# 04_MCU.net
KiCad netlist of a schematic drawn in Altium Designer
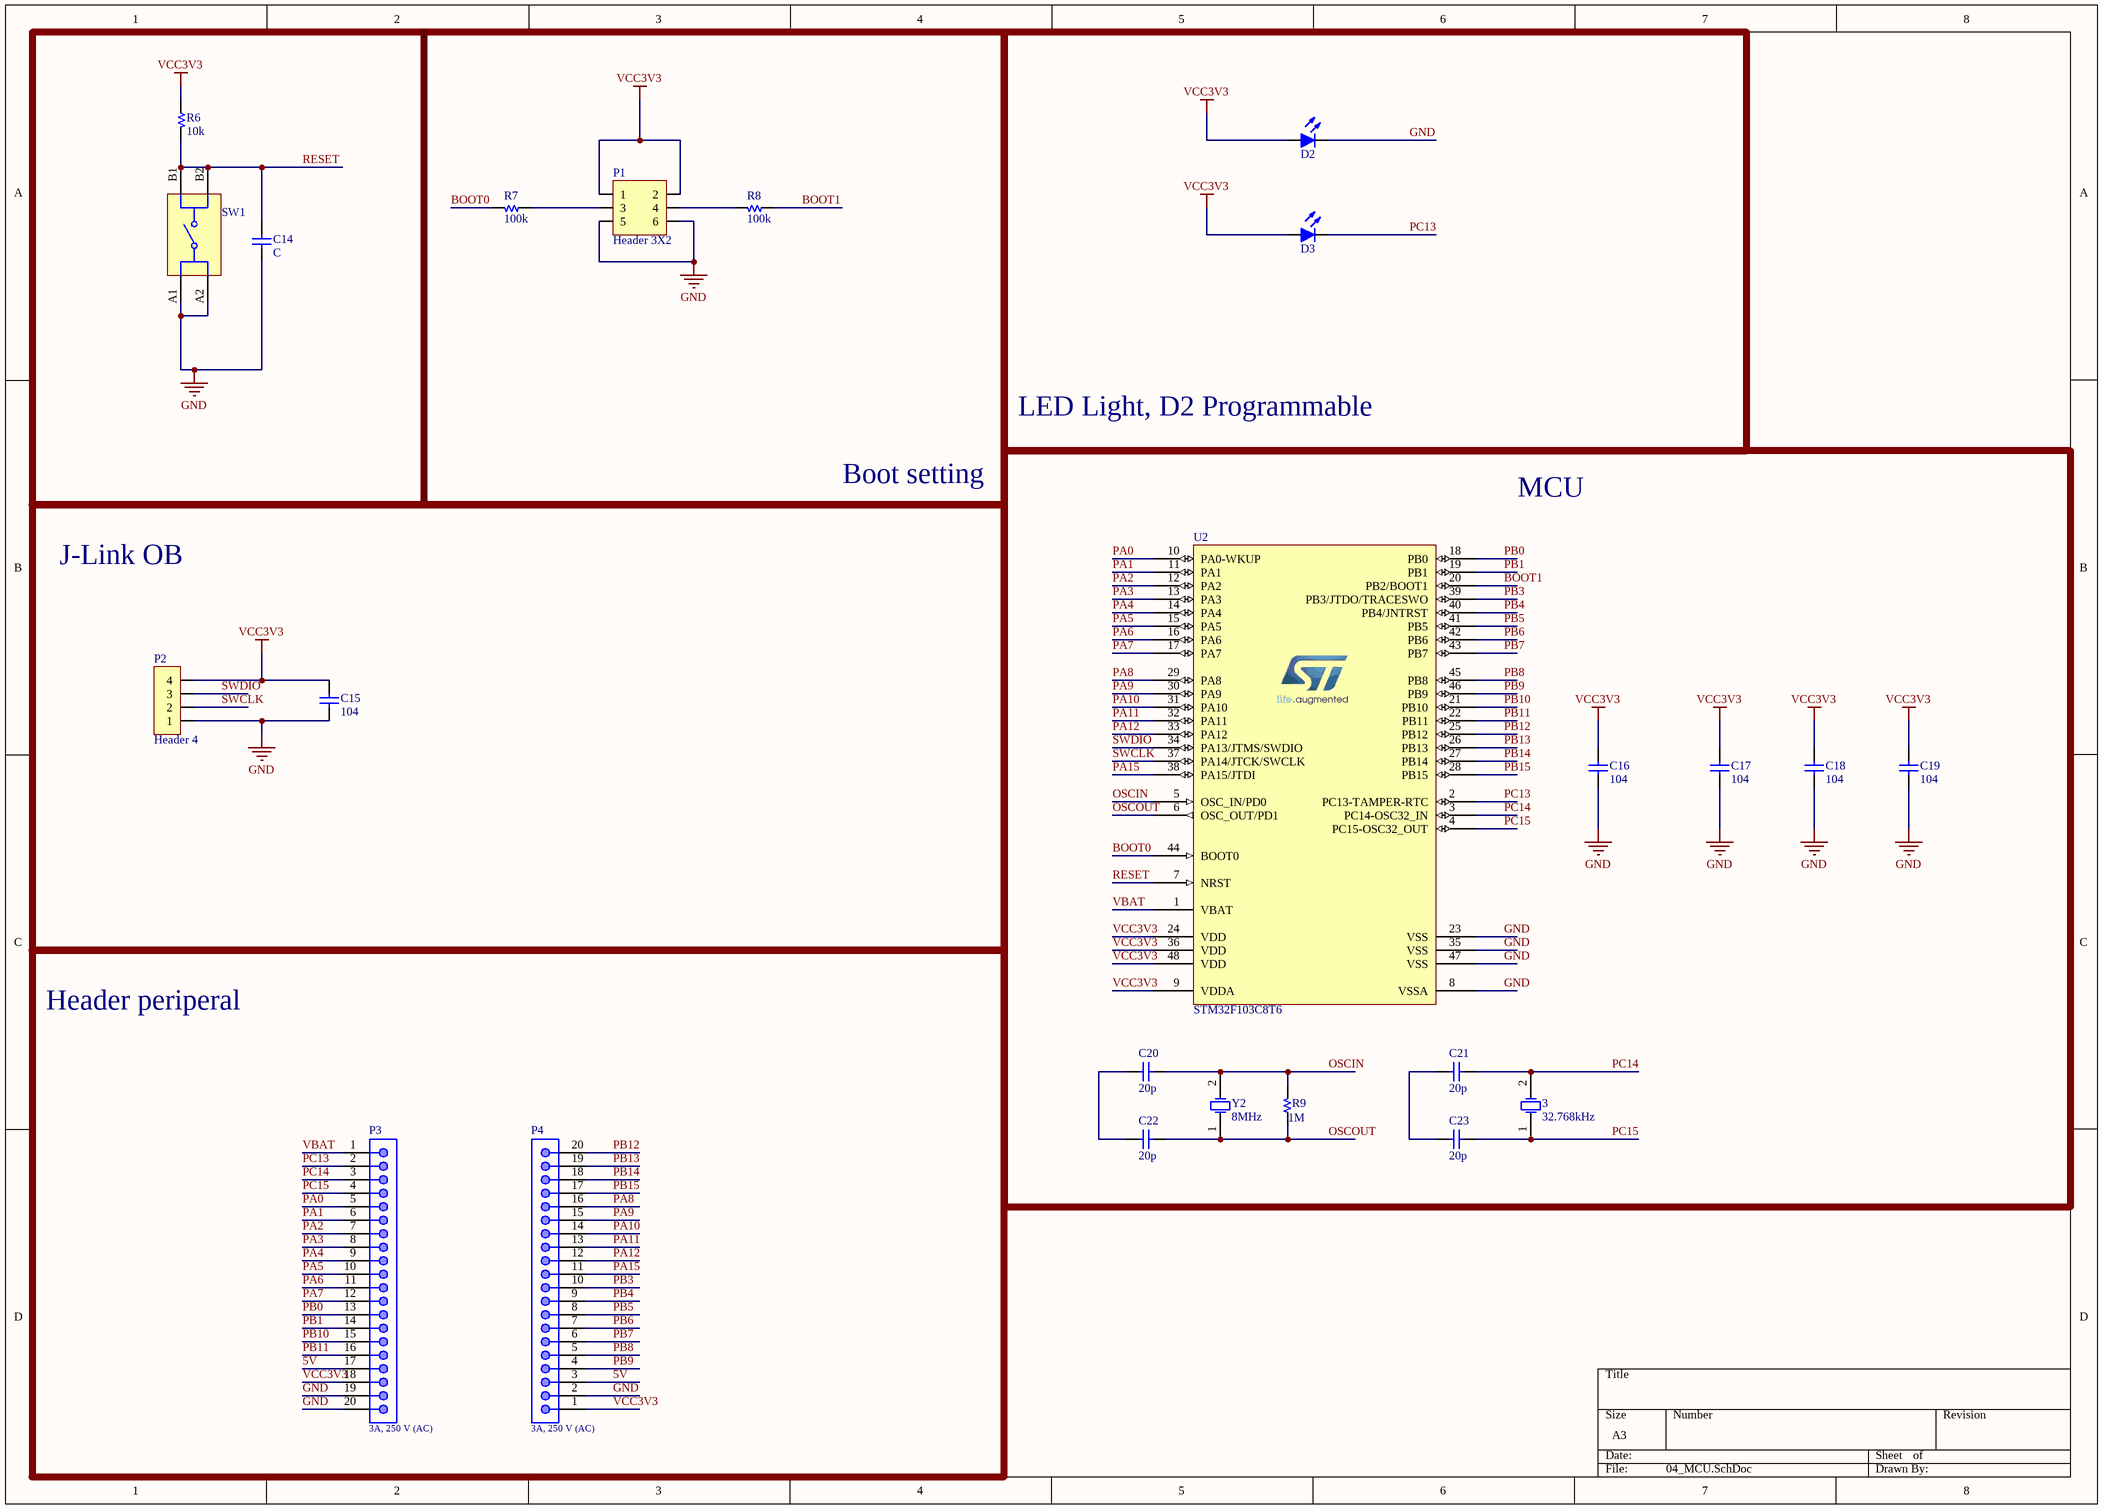
[diagram p0: 04_MCU.SchDoc]

(export (version "E")
  (design (tool "Eeschema 10.0.6"))
  (components
    (comp (ref "3")
      (value "32.768kHz")
      (footprint "XKXGI-SUA-32.768K")
      (description "32.768kHz Surface Mount Crystal 12.5pF ±20ppm ±30ppm SMD3215-2P Crystals ROHS")
      (fields (field (name "LCSC PART #") "C5213671") (field (name "MANUFACTURER") "YXC Crystal Oscillators"))
      (libsource (lib "Altium_XTAL_WATCH") (part "XKXGI-SUA-32.768K"))
    )
    (comp (ref "C14")
      (value "C")
      (footprint "C 0805")
      (description "Capacitor non-pol")
      (libsource (lib "chipfc_libs") (part "Capacitor NP"))
    )
    (comp (ref "C15")
      (value "104")
      (footprint "C 0805")
      (description "Capacitor non-pol")
      (libsource (lib "chipfc_libs") (part "Capacitor NP"))
    )
    (comp (ref "C16")
      (value "104")
      (footprint "C 0805")
      (description "Capacitor non-pol")
      (libsource (lib "chipfc_libs") (part "Capacitor NP"))
    )
    (comp (ref "C17")
      (value "104")
      (footprint "C 0805")
      (description "Capacitor non-pol")
      (libsource (lib "chipfc_libs") (part "Capacitor NP"))
    )
    (comp (ref "C18")
      (value "104")
      (footprint "C 0805")
      (description "Capacitor non-pol")
      (libsource (lib "chipfc_libs") (part "Capacitor NP"))
    )
    (comp (ref "C19")
      (value "104")
      (footprint "C 0805")
      (description "Capacitor non-pol")
      (libsource (lib "chipfc_libs") (part "Capacitor NP"))
    )
    (comp (ref "C20")
      (value "20p")
      (footprint "C 0805")
      (description "Capacitor non-pol")
      (libsource (lib "chipfc_libs") (part "Capacitor NP"))
    )
    (comp (ref "C21")
      (value "20p")
      (footprint "C 0805")
      (description "Capacitor non-pol")
      (libsource (lib "chipfc_libs") (part "Capacitor NP"))
    )
    (comp (ref "C22")
      (value "20p")
      (footprint "C 0805")
      (description "Capacitor non-pol")
      (libsource (lib "chipfc_libs") (part "Capacitor NP"))
    )
    (comp (ref "C23")
      (value "20p")
      (footprint "C 0805")
      (description "Capacitor non-pol")
      (libsource (lib "chipfc_libs") (part "Capacitor NP"))
    )
    (comp (ref "D2")
      (value "Led")
      (footprint "Led 0805")
      (description "Typical LED")
      (libsource (lib "led") (part "Led"))
    )
    (comp (ref "D3")
      (value "Led")
      (footprint "Led 0805")
      (description "Typical LED")
      (libsource (lib "led") (part "Led"))
    )
    (comp (ref "P1")
      (value "Header 3X2")
      (footprint "HDR/Header/6/DL")
      (description "Header, 3-Pin, Dual row")
      (libsource (lib "connectors") (part "Header 3X2"))
    )
    (comp (ref "P2")
      (value "Header 4")
      (footprint "HDR/Header/4")
      (description "Header, 4-Pin")
      (libsource (lib "connectors") (part "Header 4"))
    )
    (comp (ref "P3")
      (value "3A, 250 V (AC)")
      (footprint "61302011121")
      (description "WR-PHD Pin Header, THT, pitch 2.54mm, Single Row, Vertical, 20p")
      (fields
        (field (name "MANUFACTURER PART NUMBER") "61302011121")
        (field (name "MANUFACTURER") "Wurth Elektronik")
      )
      (libsource (lib "WR-PHD_Pin Header_2.54mm") (part "61302011121"))
    )
    (comp (ref "P4")
      (value "3A, 250 V (AC)")
      (footprint "61302011121")
      (description "WR-PHD Pin Header, THT, pitch 2.54mm, Single Row, Vertical, 20p")
      (fields
        (field (name "MANUFACTURER PART NUMBER") "61302011121")
        (field (name "MANUFACTURER") "Wurth Elektronik")
      )
      (libsource (lib "WR-PHD_Pin Header_2.54mm") (part "61302011121"))
    )
    (comp (ref "R6")
      (value "10k")
      (footprint "R 0805")
      (description "Resistor")
      (libsource (lib "chipfc_libs") (part "Resistor"))
    )
    (comp (ref "R7")
      (value "100k")
      (footprint "R 0805")
      (description "Resistor")
      (libsource (lib "chipfc_libs") (part "Resistor"))
    )
    (comp (ref "R8")
      (value "100k")
      (footprint "R 0805")
      (description "Resistor")
      (libsource (lib "chipfc_libs") (part "Resistor"))
    )
    (comp (ref "R9")
      (value "1M")
      (footprint "R 0805")
      (description "Resistor")
      (libsource (lib "chipfc_libs") (part "Resistor"))
    )
    (comp (ref "SW1")
      (value "430152043826")
      (footprint "WS-TASV_L6W6H4.3_4301x20438x6")
      (description "WS-TASV SMT Tact Switch, L6 x W6 x H4.3mm, 260g, SPST-NO, 12V, 50mA")
      (fields (field (name "MANUFACTURER") "Wurth Elektronik"))
      (libsource (lib "Button") (part "430152043826"))
    )
    (comp (ref "U2")
      (value "STM32F103C8T6")
      (footprint "STM32F103C8T6")
      (description "ARM Microcontrollers - MCU 32BIT Cortex M3 64KB 20KB RAM 2X12 ADC")
      (fields
        (field (name "MANUFACTURER") "STMicroelectronics")
        (field (name "MANUFACTURER PART NUMBER") "STM32F103C8T6TR")
      )
      (libsource (lib "STM32") (part "STM32F103C8T6"))
    )
    (comp (ref "Y2")
      (value "8MHz")
      (footprint "WE-XTAL_HC49/4HSMX")
      (description "WE-XTAL Quartz Crystal, SMT, HC49/4HSMX, 8MHz, +/-30ppm")
      (fields
        (field (name "MANUFACTURER PART NUMBER") "830003151")
        (field (name "MANUFACTURER") "Wurth Elektronik")
      )
      (libsource (lib "Altium_XTAL_2PIN") (part "071105086016"))
    )
  )
  (nets
    (net (code "1") (name "/5V") (class "Default")
      (node (ref "P3") (pin "17") (pinfunction "17_17") (pintype "passive"))
      (node (ref "P4") (pin "3") (pinfunction "3_3") (pintype "passive"))
    )
    (net (code "2") (name "/BOOT0") (class "Default")
      (node (ref "R7") (pin "2") (pinfunction "2_2") (pintype "passive"))
      (node (ref "U2") (pin "44") (pinfunction "BOOT0_44") (pintype "input"))
    )
    (net (code "3") (name "/BOOT1") (class "Default")
      (node (ref "R8") (pin "1") (pinfunction "1_1") (pintype "passive"))
      (node (ref "U2") (pin "20") (pinfunction "PB2/BOOT1_20") (pintype "bidirectional"))
    )
    (net (code "4") (name "/OSCIN") (class "Default")
      (node (ref "C20") (pin "1") (pinfunction "1_1") (pintype "passive"))
      (node (ref "R9") (pin "2") (pinfunction "2_2") (pintype "passive"))
      (node (ref "U2") (pin "5") (pinfunction "OSC_IN/PD0_5") (pintype "input"))
      (node (ref "Y2") (pin "2") (pinfunction "OSC2_2") (pintype "passive"))
    )
    (net (code "5") (name "/OSCOUT") (class "Default")
      (node (ref "C22") (pin "1") (pinfunction "1_1") (pintype "passive"))
      (node (ref "R9") (pin "1") (pinfunction "1_1") (pintype "passive"))
      (node (ref "U2") (pin "6") (pinfunction "OSC_OUT/PD1_6") (pintype "output"))
      (node (ref "Y2") (pin "1") (pinfunction "OSC1_1") (pintype "passive"))
    )
    (net (code "6") (name "/PA0") (class "Default")
      (node (ref "P3") (pin "5") (pinfunction "5_5") (pintype "passive"))
      (node (ref "U2") (pin "10") (pinfunction "PA0-WKUP_10") (pintype "bidirectional"))
    )
    (net (code "7") (name "/PA1") (class "Default")
      (node (ref "P3") (pin "6") (pinfunction "6_6") (pintype "passive"))
      (node (ref "U2") (pin "11") (pinfunction "PA1_11") (pintype "bidirectional"))
    )
    (net (code "8") (name "/PA2") (class "Default")
      (node (ref "P3") (pin "7") (pinfunction "7_7") (pintype "passive"))
      (node (ref "U2") (pin "12") (pinfunction "PA2_12") (pintype "bidirectional"))
    )
    (net (code "9") (name "/PA3") (class "Default")
      (node (ref "P3") (pin "8") (pinfunction "8_8") (pintype "passive"))
      (node (ref "U2") (pin "13") (pinfunction "PA3_13") (pintype "bidirectional"))
    )
    (net (code "10") (name "/PA4") (class "Default")
      (node (ref "P3") (pin "9") (pinfunction "9_9") (pintype "passive"))
      (node (ref "U2") (pin "14") (pinfunction "PA4_14") (pintype "bidirectional"))
    )
    (net (code "11") (name "/PA5") (class "Default")
      (node (ref "P3") (pin "10") (pinfunction "10_10") (pintype "passive"))
      (node (ref "U2") (pin "15") (pinfunction "PA5_15") (pintype "bidirectional"))
    )
    (net (code "12") (name "/PA6") (class "Default")
      (node (ref "P3") (pin "11") (pinfunction "11_11") (pintype "passive"))
      (node (ref "U2") (pin "16") (pinfunction "PA6_16") (pintype "bidirectional"))
    )
    (net (code "13") (name "/PA7") (class "Default")
      (node (ref "P3") (pin "12") (pinfunction "12_12") (pintype "passive"))
      (node (ref "U2") (pin "17") (pinfunction "PA7_17") (pintype "bidirectional"))
    )
    (net (code "14") (name "/PA8") (class "Default")
      (node (ref "P4") (pin "16") (pinfunction "16_16") (pintype "passive"))
      (node (ref "U2") (pin "29") (pinfunction "PA8_29") (pintype "bidirectional"))
    )
    (net (code "15") (name "/PA9") (class "Default")
      (node (ref "P4") (pin "15") (pinfunction "15_15") (pintype "passive"))
      (node (ref "U2") (pin "30") (pinfunction "PA9_30") (pintype "bidirectional"))
    )
    (net (code "16") (name "/PA10") (class "Default")
      (node (ref "P4") (pin "14") (pinfunction "14_14") (pintype "passive"))
      (node (ref "U2") (pin "31") (pinfunction "PA10_31") (pintype "bidirectional"))
    )
    (net (code "17") (name "/PA11") (class "Default")
      (node (ref "P4") (pin "13") (pinfunction "13_13") (pintype "passive"))
      (node (ref "U2") (pin "32") (pinfunction "PA11_32") (pintype "bidirectional"))
    )
    (net (code "18") (name "/PA12") (class "Default")
      (node (ref "P4") (pin "12") (pinfunction "12_12") (pintype "passive"))
      (node (ref "U2") (pin "33") (pinfunction "PA12_33") (pintype "bidirectional"))
    )
    (net (code "19") (name "/PA15") (class "Default")
      (node (ref "P4") (pin "11") (pinfunction "11_11") (pintype "passive"))
      (node (ref "U2") (pin "38") (pinfunction "PA15/JTDI_38") (pintype "bidirectional"))
    )
    (net (code "20") (name "/PB0") (class "Default")
      (node (ref "P3") (pin "13") (pinfunction "13_13") (pintype "passive"))
      (node (ref "U2") (pin "18") (pinfunction "PB0_18") (pintype "bidirectional"))
    )
    (net (code "21") (name "/PB1") (class "Default")
      (node (ref "P3") (pin "14") (pinfunction "14_14") (pintype "passive"))
      (node (ref "U2") (pin "19") (pinfunction "PB1_19") (pintype "bidirectional"))
    )
    (net (code "22") (name "/PB3") (class "Default")
      (node (ref "P4") (pin "10") (pinfunction "10_10") (pintype "passive"))
      (node (ref "U2") (pin "39") (pinfunction "PB3/JTDO/TRACESWO_39") (pintype "bidirectional"))
    )
    (net (code "23") (name "/PB4") (class "Default")
      (node (ref "P4") (pin "9") (pinfunction "9_9") (pintype "passive"))
      (node (ref "U2") (pin "40") (pinfunction "PB4/JNTRST_40") (pintype "bidirectional"))
    )
    (net (code "24") (name "/PB5") (class "Default")
      (node (ref "P4") (pin "8") (pinfunction "8_8") (pintype "passive"))
      (node (ref "U2") (pin "41") (pinfunction "PB5_41") (pintype "bidirectional"))
    )
    (net (code "25") (name "/PB6") (class "Default")
      (node (ref "P4") (pin "7") (pinfunction "7_7") (pintype "passive"))
      (node (ref "U2") (pin "42") (pinfunction "PB6_42") (pintype "bidirectional"))
    )
    (net (code "26") (name "/PB7") (class "Default")
      (node (ref "P4") (pin "6") (pinfunction "6_6") (pintype "passive"))
      (node (ref "U2") (pin "43") (pinfunction "PB7_43") (pintype "bidirectional"))
    )
    (net (code "27") (name "/PB8") (class "Default")
      (node (ref "P4") (pin "5") (pinfunction "5_5") (pintype "passive"))
      (node (ref "U2") (pin "45") (pinfunction "PB8_45") (pintype "bidirectional"))
    )
    (net (code "28") (name "/PB9") (class "Default")
      (node (ref "P4") (pin "4") (pinfunction "4_4") (pintype "passive"))
      (node (ref "U2") (pin "46") (pinfunction "PB9_46") (pintype "bidirectional"))
    )
    (net (code "29") (name "/PB10") (class "Default")
      (node (ref "P3") (pin "15") (pinfunction "15_15") (pintype "passive"))
      (node (ref "U2") (pin "21") (pinfunction "PB10_21") (pintype "bidirectional"))
    )
    (net (code "30") (name "/PB11") (class "Default")
      (node (ref "P3") (pin "16") (pinfunction "16_16") (pintype "passive"))
      (node (ref "U2") (pin "22") (pinfunction "PB11_22") (pintype "bidirectional"))
    )
    (net (code "31") (name "/PB12") (class "Default")
      (node (ref "P4") (pin "20") (pinfunction "20_20") (pintype "passive"))
      (node (ref "U2") (pin "25") (pinfunction "PB12_25") (pintype "bidirectional"))
    )
    (net (code "32") (name "/PB13") (class "Default")
      (node (ref "P4") (pin "19") (pinfunction "19_19") (pintype "passive"))
      (node (ref "U2") (pin "26") (pinfunction "PB13_26") (pintype "bidirectional"))
    )
    (net (code "33") (name "/PB14") (class "Default")
      (node (ref "P4") (pin "18") (pinfunction "18_18") (pintype "passive"))
      (node (ref "U2") (pin "27") (pinfunction "PB14_27") (pintype "bidirectional"))
    )
    (net (code "34") (name "/PB15") (class "Default")
      (node (ref "P4") (pin "17") (pinfunction "17_17") (pintype "passive"))
      (node (ref "U2") (pin "28") (pinfunction "PB15_28") (pintype "bidirectional"))
    )
    (net (code "35") (name "/PC13") (class "Default")
      (node (ref "D3") (pin "2") (pinfunction "K_2") (pintype "passive"))
      (node (ref "P3") (pin "2") (pinfunction "2_2") (pintype "passive"))
      (node (ref "U2") (pin "2") (pinfunction "PC13-TAMPER-RTC_2") (pintype "bidirectional"))
    )
    (net (code "36") (name "/PC14") (class "Default")
      (node (ref "3") (pin "2") (pinfunction "OSC2_2") (pintype "passive"))
      (node (ref "C21") (pin "1") (pinfunction "1_1") (pintype "passive"))
      (node (ref "P3") (pin "3") (pinfunction "3_3") (pintype "passive"))
      (node (ref "U2") (pin "3") (pinfunction "PC14-OSC32_IN_3") (pintype "bidirectional"))
    )
    (net (code "37") (name "/PC15") (class "Default")
      (node (ref "3") (pin "1") (pinfunction "OSC1_1") (pintype "passive"))
      (node (ref "C23") (pin "1") (pinfunction "1_1") (pintype "passive"))
      (node (ref "P3") (pin "4") (pinfunction "4_4") (pintype "passive"))
      (node (ref "U2") (pin "4") (pinfunction "PC15-OSC32_OUT_4") (pintype "bidirectional"))
    )
    (net (code "38") (name "/RESET") (class "Default")
      (node (ref "C14") (pin "1") (pinfunction "1_1") (pintype "passive"))
      (node (ref "R6") (pin "2") (pinfunction "2_2") (pintype "passive"))
      (node (ref "SW1") (pin "B1") (pinfunction "B1_B1") (pintype "passive"))
      (node (ref "SW1") (pin "B2") (pinfunction "B2_B2") (pintype "passive"))
      (node (ref "U2") (pin "7") (pinfunction "NRST_7") (pintype "input"))
    )
    (net (code "39") (name "/SWCLK") (class "Default")
      (node (ref "P2") (pin "2") (pinfunction "2_2") (pintype "passive"))
      (node (ref "U2") (pin "37") (pinfunction "PA14/JTCK/SWCLK_37") (pintype "bidirectional"))
    )
    (net (code "40") (name "/SWDIO") (class "Default")
      (node (ref "P2") (pin "3") (pinfunction "3_3") (pintype "passive"))
      (node (ref "U2") (pin "34") (pinfunction "PA13/JTMS/SWDIO_34") (pintype "bidirectional"))
    )
    (net (code "41") (name "/VBAT") (class "Default")
      (node (ref "P3") (pin "1") (pinfunction "1_1") (pintype "passive"))
      (node (ref "U2") (pin "1") (pinfunction "VBAT_1") (pintype "power_in"))
    )
    (net (code "42") (name "GND") (class "Default")
      (node (ref "C14") (pin "2") (pinfunction "2_2") (pintype "passive"))
      (node (ref "C15") (pin "2") (pinfunction "2_2") (pintype "passive"))
      (node (ref "C16") (pin "1") (pinfunction "1_1") (pintype "passive"))
      (node (ref "C17") (pin "1") (pinfunction "1_1") (pintype "passive"))
      (node (ref "C18") (pin "1") (pinfunction "1_1") (pintype "passive"))
      (node (ref "C19") (pin "1") (pinfunction "1_1") (pintype "passive"))
      (node (ref "D2") (pin "2") (pinfunction "K_2") (pintype "passive"))
      (node (ref "P1") (pin "5") (pinfunction "5_5") (pintype "passive"))
      (node (ref "P1") (pin "6") (pinfunction "6_6") (pintype "passive"))
      (node (ref "P2") (pin "1") (pinfunction "1_1") (pintype "passive"))
      (node (ref "P3") (pin "19") (pinfunction "19_19") (pintype "passive"))
      (node (ref "P3") (pin "20") (pinfunction "20_20") (pintype "passive"))
      (node (ref "P4") (pin "2") (pinfunction "2_2") (pintype "passive"))
      (node (ref "SW1") (pin "A1") (pinfunction "A1_A1") (pintype "passive"))
      (node (ref "SW1") (pin "A2") (pinfunction "A2_A2") (pintype "passive"))
      (node (ref "U2") (pin "23") (pinfunction "VSS_23") (pintype "power_in"))
      (node (ref "U2") (pin "35") (pinfunction "VSS_35") (pintype "power_in"))
      (node (ref "U2") (pin "47") (pinfunction "VSS_47") (pintype "power_in"))
      (node (ref "U2") (pin "8") (pinfunction "VSSA_8") (pintype "power_in"))
    )
    (net (code "43") (name "Net-(C20-Pad2)") (class "Default")
      (node (ref "C20") (pin "2") (pinfunction "2_2") (pintype "passive"))
      (node (ref "C22") (pin "2") (pinfunction "2_2") (pintype "passive"))
    )
    (net (code "44") (name "Net-(C21-Pad2)") (class "Default")
      (node (ref "C21") (pin "2") (pinfunction "2_2") (pintype "passive"))
      (node (ref "C23") (pin "2") (pinfunction "2_2") (pintype "passive"))
    )
    (net (code "45") (name "Net-(P1-Pad3)") (class "Default")
      (node (ref "P1") (pin "3") (pinfunction "3_3") (pintype "passive"))
      (node (ref "R7") (pin "1") (pinfunction "1_1") (pintype "passive"))
    )
    (net (code "46") (name "Net-(P1-Pad4)") (class "Default")
      (node (ref "P1") (pin "4") (pinfunction "4_4") (pintype "passive"))
      (node (ref "R8") (pin "2") (pinfunction "2_2") (pintype "passive"))
    )
    (net (code "47") (name "VCC3V3") (class "Default")
      (node (ref "C15") (pin "1") (pinfunction "1_1") (pintype "passive"))
      (node (ref "C16") (pin "2") (pinfunction "2_2") (pintype "passive"))
      (node (ref "C17") (pin "2") (pinfunction "2_2") (pintype "passive"))
      (node (ref "C18") (pin "2") (pinfunction "2_2") (pintype "passive"))
      (node (ref "C19") (pin "2") (pinfunction "2_2") (pintype "passive"))
      (node (ref "D2") (pin "1") (pinfunction "A_1") (pintype "passive"))
      (node (ref "D3") (pin "1") (pinfunction "A_1") (pintype "passive"))
      (node (ref "P1") (pin "1") (pinfunction "1_1") (pintype "passive"))
      (node (ref "P1") (pin "2") (pinfunction "2_2") (pintype "passive"))
      (node (ref "P2") (pin "4") (pinfunction "4_4") (pintype "passive"))
      (node (ref "P3") (pin "18") (pinfunction "18_18") (pintype "passive"))
      (node (ref "P4") (pin "1") (pinfunction "1_1") (pintype "passive"))
      (node (ref "R6") (pin "1") (pinfunction "1_1") (pintype "passive"))
      (node (ref "U2") (pin "24") (pinfunction "VDD_24") (pintype "power_in"))
      (node (ref "U2") (pin "36") (pinfunction "VDD_36") (pintype "power_in"))
      (node (ref "U2") (pin "48") (pinfunction "VDD_48") (pintype "power_in"))
      (node (ref "U2") (pin "9") (pinfunction "VDDA_9") (pintype "power_in"))
    )
  )
)
